# 407-cpu.net
KiCad netlist of a schematic drawn in Altium Designer
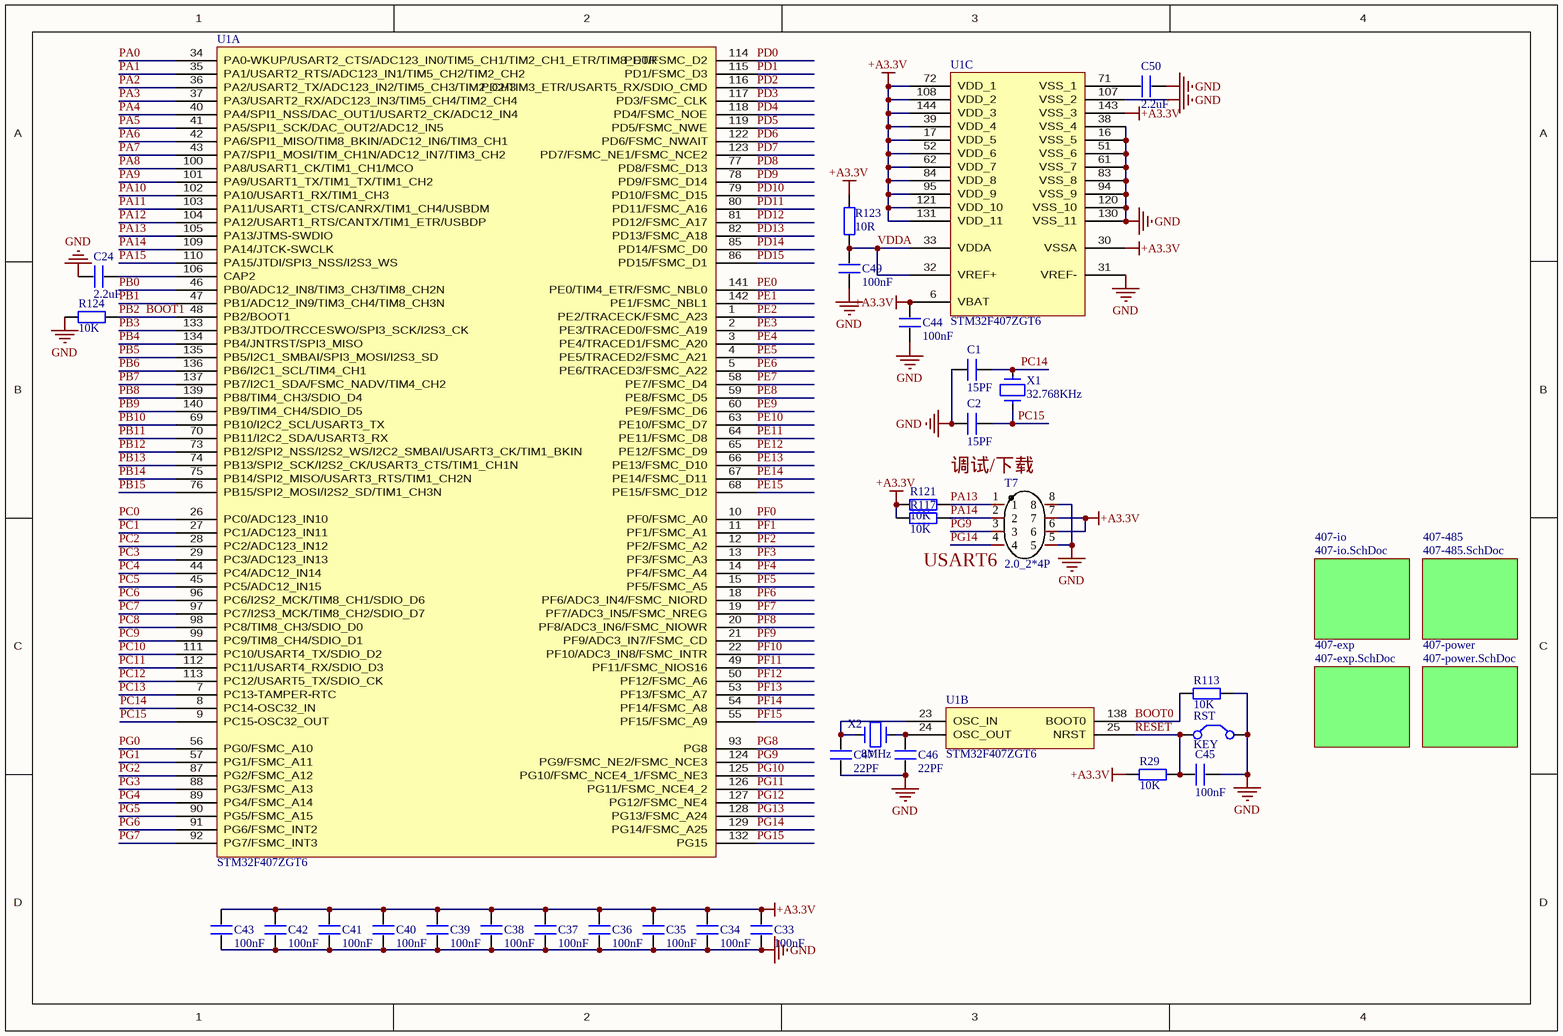
[diagram p0: 407-cpu .schdoc]

(export (version "E")
  (design (tool "Eeschema 10.0.6"))
  (components
    (comp (ref "C1") (value "15PF") (libsource (lib "驱动库") (part "C")))
    (comp (ref "C2") (value "15PF") (libsource (lib "驱动库") (part "C")))
    (comp (ref "C24") (value "2.2uF") (libsource (lib "驱动库") (part "C")))
    (comp (ref "C33") (value "100nF") (libsource (lib "驱动库") (part "C")))
    (comp (ref "C34") (value "100nF") (libsource (lib "驱动库") (part "C")))
    (comp (ref "C35") (value "100nF") (libsource (lib "驱动库") (part "C")))
    (comp (ref "C36") (value "100nF") (libsource (lib "驱动库") (part "C")))
    (comp (ref "C37") (value "100nF") (libsource (lib "驱动库") (part "C")))
    (comp (ref "C38") (value "100nF") (libsource (lib "驱动库") (part "C")))
    (comp (ref "C39") (value "100nF") (libsource (lib "驱动库") (part "C")))
    (comp (ref "C40") (value "100nF") (libsource (lib "驱动库") (part "C")))
    (comp (ref "C41") (value "100nF") (libsource (lib "驱动库") (part "C")))
    (comp (ref "C42") (value "100nF") (libsource (lib "驱动库") (part "C")))
    (comp (ref "C43") (value "100nF") (libsource (lib "驱动库") (part "C")))
    (comp (ref "C44") (value "100nF") (libsource (lib "驱动库") (part "C")))
    (comp (ref "C45") (value "100nF") (libsource (lib "驱动库") (part "C")))
    (comp (ref "C46") (value "22PF") (libsource (lib "驱动库") (part "C")))
    (comp (ref "C47") (value "22PF") (libsource (lib "驱动库") (part "C")))
    (comp (ref "C49") (value "100nF") (libsource (lib "驱动库") (part "C")))
    (comp (ref "C50") (value "2.2uF") (libsource (lib "驱动库") (part "C")))
    (comp (ref "R29") (value "10K") (description "Resistor") (libsource (lib "STM32F103ZE") (part "Res2")))
    (comp (ref "R113") (value "10K") (description "Resistor") (libsource (lib "STM32F103ZE") (part "Res2")))
    (comp (ref "R117") (value "10K") (description "Resistor") (libsource (lib "") (part "Res2_1")))
    (comp (ref "R121") (value "10K") (description "Resistor") (libsource (lib "") (part "Res2_1")))
    (comp (ref "R123") (value "10R") (description "Resistor") (libsource (lib "") (part "Res2_2")))
    (comp (ref "R124") (value "10K") (description "Resistor") (libsource (lib "STM32F103ZE") (part "Res2")))
    (comp (ref "RST")
      (value "KEY")
      (description "Jumper Wire")
      (fields (field (name "PUBLISHER") "Altium Limited"))
      (libsource (lib "STM32F103ZE") (part "Jumper"))
    )
    (comp (ref "T7")
      (value "2.0_2*4P")
      (footprint "2.0_2*4P")
      (libsource (lib "tianjin_2023") (part "2.0_2*4P"))
    )
    (comp (ref "U1") (value "STM32F407ZGT6") (libsource (lib "STM32F103ZE") (part "STM32F103ZET6_1")))
    (comp (ref "X1")
      (value "32.768KHz")
      (description "Crystal Oscillator")
      (libsource (lib "STM32F103ZE") (part "XTAL"))
    )
    (comp (ref "X2")
      (value "8MHz")
      (description "Crystal Oscillator")
      (libsource (lib "STM32F103ZE") (part "XTAL"))
    )
  )
  (nets
    (net (code "1") (name "+A3.3V") (class "Default")
      (node (ref "C33") (pin "2") (pintype "passive"))
      (node (ref "C34") (pin "2") (pintype "passive"))
      (node (ref "C35") (pin "2") (pintype "passive"))
      (node (ref "C36") (pin "2") (pintype "passive"))
      (node (ref "C37") (pin "2") (pintype "passive"))
      (node (ref "C38") (pin "2") (pintype "passive"))
      (node (ref "C39") (pin "2") (pintype "passive"))
      (node (ref "C40") (pin "2") (pintype "passive"))
      (node (ref "C41") (pin "2") (pintype "passive"))
      (node (ref "C42") (pin "2") (pintype "passive"))
      (node (ref "C43") (pin "2") (pintype "passive"))
      (node (ref "C44") (pin "2") (pintype "passive"))
      (node (ref "R117") (pin "2") (pinfunction "2_2") (pintype "passive"))
      (node (ref "R121") (pin "2") (pinfunction "2_2") (pintype "passive"))
      (node (ref "R123") (pin "1") (pinfunction "1_1") (pintype "passive"))
      (node (ref "R29") (pin "1") (pinfunction "1_1") (pintype "passive"))
      (node (ref "T7") (pin "6") (pinfunction "6_6") (pintype "passive"))
      (node (ref "T7") (pin "7") (pinfunction "7_7") (pintype "passive"))
      (node (ref "U1") (pin "108") (pinfunction "VDD_2_108") (pintype "passive"))
      (node (ref "U1") (pin "121") (pinfunction "VDD_10_121") (pintype "passive"))
      (node (ref "U1") (pin "131") (pinfunction "VDD_11_131") (pintype "passive"))
      (node (ref "U1") (pin "143") (pinfunction "VSS_3_143") (pintype "passive"))
      (node (ref "U1") (pin "144") (pinfunction "VDD_3_144") (pintype "passive"))
      (node (ref "U1") (pin "17") (pinfunction "VDD_5_17") (pintype "passive"))
      (node (ref "U1") (pin "30") (pinfunction "VSSA_30") (pintype "passive"))
      (node (ref "U1") (pin "39") (pinfunction "VDD_4_39") (pintype "passive"))
      (node (ref "U1") (pin "52") (pinfunction "VDD_6_52") (pintype "passive"))
      (node (ref "U1") (pin "6") (pinfunction "VBAT_6") (pintype "passive"))
      (node (ref "U1") (pin "62") (pinfunction "VDD_7_62") (pintype "passive"))
      (node (ref "U1") (pin "72") (pinfunction "VDD_1_72") (pintype "passive"))
      (node (ref "U1") (pin "84") (pinfunction "VDD_8_84") (pintype "passive"))
      (node (ref "U1") (pin "95") (pinfunction "VDD_9_95") (pintype "passive"))
    )
    (net (code "3") (name "/BOOT0") (class "Default")
      (node (ref "R113") (pin "1") (pinfunction "1_1") (pintype "passive"))
      (node (ref "U1") (pin "138") (pinfunction "BOOT0_138") (pintype "passive"))
    )
    (net (code "4") (name "/BOOT1") (class "Default")
      (node (ref "R124") (pin "2") (pinfunction "2_2") (pintype "passive"))
      (node (ref "U1") (pin "48") (pinfunction "PB2/BOOT1_48") (pintype "passive"))
    )
    (net (code "5") (name "/PA0") (class "Default")
      (node (ref "U1") (pin "34") (pinfunction "PA0-WKUP/USART2_CTS/ADC123_IN0/TIM5_CH1/TIM2_CH1_ETR/TIM8_ETR_34") (pintype "passive"))
    )
    (net (code "6") (name "/PA1") (class "Default")
      (node (ref "U1") (pin "35") (pinfunction "PA1/USART2_RTS/ADC123_IN1/TIM5_CH2/TIM2_CH2_35") (pintype "passive"))
    )
    (net (code "7") (name "/PA2") (class "Default")
      (node (ref "U1") (pin "36") (pinfunction "PA2/USART2_TX/ADC123_IN2/TIM5_CH3/TIM2_CH3_36") (pintype "passive"))
    )
    (net (code "8") (name "/PA3") (class "Default")
      (node (ref "U1") (pin "37") (pinfunction "PA3/USART2_RX/ADC123_IN3/TIM5_CH4/TIM2_CH4_37") (pintype "passive"))
    )
    (net (code "9") (name "/PA4") (class "Default")
      (node (ref "U1") (pin "40") (pinfunction "PA4/SPI1_NSS/DAC_OUT1/USART2_CK/ADC12_IN4_40") (pintype "passive"))
    )
    (net (code "10") (name "/PA5") (class "Default")
      (node (ref "U1") (pin "41") (pinfunction "PA5/SPI1_SCK/DAC_OUT2/ADC12_IN5_41") (pintype "passive"))
    )
    (net (code "11") (name "/PA6") (class "Default")
      (node (ref "U1") (pin "42") (pinfunction "PA6/SPI1_MISO/TIM8_BKIN/ADC12_IN6/TIM3_CH1_42") (pintype "passive"))
    )
    (net (code "12") (name "/PA7") (class "Default")
      (node (ref "U1") (pin "43") (pinfunction "PA7/SPI1_MOSI/TIM_CH1N/ADC12_IN7/TIM3_CH2_43") (pintype "passive"))
    )
    (net (code "13") (name "/PA8") (class "Default")
      (node (ref "U1") (pin "100") (pinfunction "PA8/USART1_CK/TIM1_CH1/MCO_100") (pintype "passive"))
    )
    (net (code "14") (name "/PA9") (class "Default")
      (node (ref "U1") (pin "101") (pinfunction "PA9/USART1_TX/TIM1_TX/TIM1_CH2_101") (pintype "passive"))
    )
    (net (code "15") (name "/PA10") (class "Default")
      (node (ref "U1") (pin "102") (pinfunction "PA10/USART1_RX/TIM1_CH3_102") (pintype "passive"))
    )
    (net (code "16") (name "/PA11") (class "Default")
      (node (ref "U1") (pin "103") (pinfunction "PA11/USART1_CTS/CANRX/TIM1_CH4/USBDM_103") (pintype "passive"))
    )
    (net (code "17") (name "/PA12") (class "Default")
      (node (ref "U1") (pin "104") (pinfunction "PA12/USART1_RTS/CANTX/TIM1_ETR/USBDP_104") (pintype "passive"))
    )
    (net (code "18") (name "/PA13") (class "Default")
      (node (ref "R121") (pin "1") (pinfunction "1_1") (pintype "passive"))
      (node (ref "T7") (pin "1") (pinfunction "1_1") (pintype "passive"))
      (node (ref "U1") (pin "105") (pinfunction "PA13/JTMS-SWDIO_105") (pintype "passive"))
    )
    (net (code "19") (name "/PA14") (class "Default")
      (node (ref "R117") (pin "1") (pinfunction "1_1") (pintype "passive"))
      (node (ref "T7") (pin "2") (pinfunction "2_2") (pintype "passive"))
      (node (ref "U1") (pin "109") (pinfunction "PA14/JTCK-SWCLK_109") (pintype "passive"))
    )
    (net (code "20") (name "/PA15") (class "Default")
      (node (ref "U1") (pin "110") (pinfunction "PA15/JTDI/SPI3_NSS/I2S3_WS_110") (pintype "passive"))
    )
    (net (code "21") (name "/PB0") (class "Default")
      (node (ref "U1") (pin "46") (pinfunction "PB0/ADC12_IN8/TIM3_CH3/TIM8_CH2N_46") (pintype "passive"))
    )
    (net (code "22") (name "/PB1") (class "Default")
      (node (ref "U1") (pin "47") (pinfunction "PB1/ADC12_IN9/TIM3_CH4/TIM8_CH3N_47") (pintype "passive"))
    )
    (net (code "23") (name "/PB3") (class "Default")
      (node (ref "U1") (pin "133") (pinfunction "PB3/JTDO/TRCCESWO/SPI3_SCK/I2S3_CK_133") (pintype "passive"))
    )
    (net (code "24") (name "/PB4") (class "Default")
      (node (ref "U1") (pin "134") (pinfunction "PB4/JNTRST/SPI3_MISO_134") (pintype "passive"))
    )
    (net (code "25") (name "/PB5") (class "Default")
      (node (ref "U1") (pin "135") (pinfunction "PB5/I2C1_SMBAI/SPI3_MOSI/I2S3_SD_135") (pintype "passive"))
    )
    (net (code "26") (name "/PB6") (class "Default")
      (node (ref "U1") (pin "136") (pinfunction "PB6/I2C1_SCL/TIM4_CH1_136") (pintype "passive"))
    )
    (net (code "27") (name "/PB7") (class "Default")
      (node (ref "U1") (pin "137") (pinfunction "PB7/I2C1_SDA/FSMC_NADV/TIM4_CH2_137") (pintype "passive"))
    )
    (net (code "28") (name "/PB8") (class "Default")
      (node (ref "U1") (pin "139") (pinfunction "PB8/TIM4_CH3/SDIO_D4_139") (pintype "passive"))
    )
    (net (code "29") (name "/PB9") (class "Default")
      (node (ref "U1") (pin "140") (pinfunction "PB9/TIM4_CH4/SDIO_D5_140") (pintype "passive"))
    )
    (net (code "30") (name "/PB10") (class "Default")
      (node (ref "U1") (pin "69") (pinfunction "PB10/I2C2_SCL/USART3_TX_69") (pintype "passive"))
    )
    (net (code "31") (name "/PB11") (class "Default")
      (node (ref "U1") (pin "70") (pinfunction "PB11/I2C2_SDA/USART3_RX_70") (pintype "passive"))
    )
    (net (code "32") (name "/PB12") (class "Default")
      (node (ref "U1") (pin "73") (pinfunction "PB12/SPI2_NSS/I2S2_WS/I2C2_SMBAI/USART3_CK/TIM1_BKIN_73") (pintype "passive"))
    )
    (net (code "33") (name "/PB13") (class "Default")
      (node (ref "U1") (pin "74") (pinfunction "PB13/SPI2_SCK/I2S2_CK/USART3_CTS/TIM1_CH1N_74") (pintype "passive"))
    )
    (net (code "34") (name "/PB14") (class "Default")
      (node (ref "U1") (pin "75") (pinfunction "PB14/SPI2_MISO/USART3_RTS/TIM1_CH2N_75") (pintype "passive"))
    )
    (net (code "35") (name "/PB15") (class "Default")
      (node (ref "U1") (pin "76") (pinfunction "PB15/SPI2_MOSI/I2S2_SD/TIM1_CH3N_76") (pintype "passive"))
    )
    (net (code "36") (name "/PC0") (class "Default")
      (node (ref "U1") (pin "26") (pinfunction "PC0/ADC123_IN10_26") (pintype "passive"))
    )
    (net (code "37") (name "/PC1") (class "Default")
      (node (ref "U1") (pin "27") (pinfunction "PC1/ADC123_IN11_27") (pintype "passive"))
    )
    (net (code "38") (name "/PC2") (class "Default")
      (node (ref "U1") (pin "28") (pinfunction "PC2/ADC123_IN12_28") (pintype "passive"))
    )
    (net (code "39") (name "/PC3") (class "Default")
      (node (ref "U1") (pin "29") (pinfunction "PC3/ADC123_IN13_29") (pintype "passive"))
    )
    (net (code "40") (name "/PC4") (class "Default")
      (node (ref "U1") (pin "44") (pinfunction "PC4/ADC12_IN14_44") (pintype "passive"))
    )
    (net (code "41") (name "/PC5") (class "Default")
      (node (ref "U1") (pin "45") (pinfunction "PC5/ADC12_IN15_45") (pintype "passive"))
    )
    (net (code "42") (name "/PC6") (class "Default")
      (node (ref "U1") (pin "96") (pinfunction "PC6/I2S2_MCK/TIM8_CH1/SDIO_D6_96") (pintype "passive"))
    )
    (net (code "43") (name "/PC7") (class "Default")
      (node (ref "U1") (pin "97") (pinfunction "PC7/I2S3_MCK/TIM8_CH2/SDIO_D7_97") (pintype "passive"))
    )
    (net (code "44") (name "/PC8") (class "Default")
      (node (ref "U1") (pin "98") (pinfunction "PC8/TIM8_CH3/SDIO_D0_98") (pintype "passive"))
    )
    (net (code "45") (name "/PC9") (class "Default")
      (node (ref "U1") (pin "99") (pinfunction "PC9/TIM8_CH4/SDIO_D1_99") (pintype "passive"))
    )
    (net (code "46") (name "/PC10") (class "Default")
      (node (ref "U1") (pin "111") (pinfunction "PC10/USART4_TX/SDIO_D2_111") (pintype "passive"))
    )
    (net (code "47") (name "/PC11") (class "Default")
      (node (ref "U1") (pin "112") (pinfunction "PC11/USART4_RX/SDIO_D3_112") (pintype "passive"))
    )
    (net (code "48") (name "/PC12") (class "Default")
      (node (ref "U1") (pin "113") (pinfunction "PC12/USART5_TX/SDIO_CK_113") (pintype "passive"))
    )
    (net (code "49") (name "/PC13") (class "Default")
      (node (ref "U1") (pin "7") (pinfunction "PC13-TAMPER-RTC_7") (pintype "passive"))
    )
    (net (code "50") (name "/PC14") (class "Default")
      (node (ref "C1") (pin "1") (pintype "passive"))
      (node (ref "U1") (pin "8") (pinfunction "PC14-OSC32_IN_8") (pintype "passive"))
      (node (ref "X1") (pin "1") (pinfunction "1_1") (pintype "passive"))
    )
    (net (code "51") (name "/PC15") (class "Default")
      (node (ref "C2") (pin "1") (pintype "passive"))
      (node (ref "U1") (pin "9") (pinfunction "PC15-OSC32_OUT_9") (pintype "passive"))
      (node (ref "X1") (pin "2") (pinfunction "2_2") (pintype "passive"))
    )
    (net (code "52") (name "/PD0") (class "Default")
      (node (ref "U1") (pin "114") (pinfunction "PD0/FSMC_D2_114") (pintype "passive"))
    )
    (net (code "53") (name "/PD1") (class "Default")
      (node (ref "U1") (pin "115") (pinfunction "PD1/FSMC_D3_115") (pintype "passive"))
    )
    (net (code "54") (name "/PD2") (class "Default")
      (node (ref "U1") (pin "116") (pinfunction "PD2/TIM3_ETR/USART5_RX/SDIO_CMD_116") (pintype "passive"))
    )
    (net (code "55") (name "/PD3") (class "Default")
      (node (ref "U1") (pin "117") (pinfunction "PD3/FSMC_CLK_117") (pintype "passive"))
    )
    (net (code "56") (name "/PD4") (class "Default")
      (node (ref "U1") (pin "118") (pinfunction "PD4/FSMC_NOE_118") (pintype "passive"))
    )
    (net (code "57") (name "/PD5") (class "Default")
      (node (ref "U1") (pin "119") (pinfunction "PD5/FSMC_NWE_119") (pintype "passive"))
    )
    (net (code "58") (name "/PD6") (class "Default")
      (node (ref "U1") (pin "122") (pinfunction "PD6/FSMC_NWAIT_122") (pintype "passive"))
    )
    (net (code "59") (name "/PD7") (class "Default")
      (node (ref "U1") (pin "123") (pinfunction "PD7/FSMC_NE1/FSMC_NCE2_123") (pintype "passive"))
    )
    (net (code "60") (name "/PD8") (class "Default")
      (node (ref "U1") (pin "77") (pinfunction "PD8/FSMC_D13_77") (pintype "passive"))
    )
    (net (code "61") (name "/PD9") (class "Default")
      (node (ref "U1") (pin "78") (pinfunction "PD9/FSMC_D14_78") (pintype "passive"))
    )
    (net (code "62") (name "/PD10") (class "Default")
      (node (ref "U1") (pin "79") (pinfunction "PD10/FSMC_D15_79") (pintype "passive"))
    )
    (net (code "63") (name "/PD11") (class "Default")
      (node (ref "U1") (pin "80") (pinfunction "PD11/FSMC_A16_80") (pintype "passive"))
    )
    (net (code "64") (name "/PD12") (class "Default")
      (node (ref "U1") (pin "81") (pinfunction "PD12/FSMC_A17_81") (pintype "passive"))
    )
    (net (code "65") (name "/PD13") (class "Default")
      (node (ref "U1") (pin "82") (pinfunction "PD13/FSMC_A18_82") (pintype "passive"))
    )
    (net (code "66") (name "/PD14") (class "Default")
      (node (ref "U1") (pin "85") (pinfunction "PD14/FSMC_D0_85") (pintype "passive"))
    )
    (net (code "67") (name "/PD15") (class "Default")
      (node (ref "U1") (pin "86") (pinfunction "PD15/FSMC_D1_86") (pintype "passive"))
    )
    (net (code "68") (name "/PE0") (class "Default")
      (node (ref "U1") (pin "141") (pinfunction "PE0/TIM4_ETR/FSMC_NBL0_141") (pintype "passive"))
    )
    (net (code "69") (name "/PE1") (class "Default")
      (node (ref "U1") (pin "142") (pinfunction "PE1/FSMC_NBL1_142") (pintype "passive"))
    )
    (net (code "70") (name "/PE2") (class "Default")
      (node (ref "U1") (pin "1") (pinfunction "PE2/TRACECK/FSMC_A23_1") (pintype "passive"))
    )
    (net (code "71") (name "/PE3") (class "Default")
      (node (ref "U1") (pin "2") (pinfunction "PE3/TRACED0/FSMC_A19_2") (pintype "passive"))
    )
    (net (code "72") (name "/PE4") (class "Default")
      (node (ref "U1") (pin "3") (pinfunction "PE4/TRACED1/FSMC_A20_3") (pintype "passive"))
    )
    (net (code "73") (name "/PE5") (class "Default")
      (node (ref "U1") (pin "4") (pinfunction "PE5/TRACED2/FSMC_A21_4") (pintype "passive"))
    )
    (net (code "74") (name "/PE6") (class "Default")
      (node (ref "U1") (pin "5") (pinfunction "PE6/TRACED3/FSMC_A22_5") (pintype "passive"))
    )
    (net (code "75") (name "/PE7") (class "Default")
      (node (ref "U1") (pin "58") (pinfunction "PE7/FSMC_D4_58") (pintype "passive"))
    )
    (net (code "76") (name "/PE8") (class "Default")
      (node (ref "U1") (pin "59") (pinfunction "PE8/FSMC_D5_59") (pintype "passive"))
    )
    (net (code "77") (name "/PE9") (class "Default")
      (node (ref "U1") (pin "60") (pinfunction "PE9/FSMC_D6_60") (pintype "passive"))
    )
    (net (code "78") (name "/PE10") (class "Default")
      (node (ref "U1") (pin "63") (pinfunction "PE10/FSMC_D7_63") (pintype "passive"))
    )
    (net (code "79") (name "/PE11") (class "Default")
      (node (ref "U1") (pin "64") (pinfunction "PE11/FSMC_D8_64") (pintype "passive"))
    )
    (net (code "80") (name "/PE12") (class "Default")
      (node (ref "U1") (pin "65") (pinfunction "PE12/FSMC_D9_65") (pintype "passive"))
    )
    (net (code "81") (name "/PE13") (class "Default")
      (node (ref "U1") (pin "66") (pinfunction "PE13/FSMC_D10_66") (pintype "passive"))
    )
    (net (code "82") (name "/PE14") (class "Default")
      (node (ref "U1") (pin "67") (pinfunction "PE14/FSMC_D11_67") (pintype "passive"))
    )
    (net (code "83") (name "/PE15") (class "Default")
      (node (ref "U1") (pin "68") (pinfunction "PE15/FSMC_D12_68") (pintype "passive"))
    )
    (net (code "84") (name "/PF0") (class "Default")
      (node (ref "U1") (pin "10") (pinfunction "PF0/FSMC_A0_10") (pintype "passive"))
    )
    (net (code "85") (name "/PF1") (class "Default")
      (node (ref "U1") (pin "11") (pinfunction "PF1/FSMC_A1_11") (pintype "passive"))
    )
    (net (code "86") (name "/PF2") (class "Default")
      (node (ref "U1") (pin "12") (pinfunction "PF2/FSMC_A2_12") (pintype "passive"))
    )
    (net (code "87") (name "/PF3") (class "Default")
      (node (ref "U1") (pin "13") (pinfunction "PF3/FSMC_A3_13") (pintype "passive"))
    )
    (net (code "88") (name "/PF4") (class "Default")
      (node (ref "U1") (pin "14") (pinfunction "PF4/FSMC_A4_14") (pintype "passive"))
    )
    (net (code "89") (name "/PF5") (class "Default")
      (node (ref "U1") (pin "15") (pinfunction "PF5/FSMC_A5_15") (pintype "passive"))
    )
    (net (code "90") (name "/PF6") (class "Default")
      (node (ref "U1") (pin "18") (pinfunction "PF6/ADC3_IN4/FSMC_NIORD_18") (pintype "passive"))
    )
    (net (code "91") (name "/PF7") (class "Default")
      (node (ref "U1") (pin "19") (pinfunction "PF7/ADC3_IN5/FSMC_NREG_19") (pintype "passive"))
    )
    (net (code "92") (name "/PF8") (class "Default")
      (node (ref "U1") (pin "20") (pinfunction "PF8/ADC3_IN6/FSMC_NIOWR_20") (pintype "passive"))
    )
    (net (code "93") (name "/PF9") (class "Default")
      (node (ref "U1") (pin "21") (pinfunction "PF9/ADC3_IN7/FSMC_CD_21") (pintype "passive"))
    )
    (net (code "94") (name "/PF10") (class "Default")
      (node (ref "U1") (pin "22") (pinfunction "PF10/ADC3_IN8/FSMC_INTR_22") (pintype "passive"))
    )
    (net (code "95") (name "/PF11") (class "Default")
      (node (ref "U1") (pin "49") (pinfunction "PF11/FSMC_NIOS16_49") (pintype "passive"))
    )
    (net (code "96") (name "/PF12") (class "Default")
      (node (ref "U1") (pin "50") (pinfunction "PF12/FSMC_A6_50") (pintype "passive"))
    )
    (net (code "97") (name "/PF13") (class "Default")
      (node (ref "U1") (pin "53") (pinfunction "PF13/FSMC_A7_53") (pintype "passive"))
    )
    (net (code "98") (name "/PF14") (class "Default")
      (node (ref "U1") (pin "54") (pinfunction "PF14/FSMC_A8_54") (pintype "passive"))
    )
    (net (code "99") (name "/PF15") (class "Default")
      (node (ref "U1") (pin "55") (pinfunction "PF15/FSMC_A9_55") (pintype "passive"))
    )
    (net (code "100") (name "/PG0") (class "Default")
      (node (ref "U1") (pin "56") (pinfunction "PG0/FSMC_A10_56") (pintype "passive"))
    )
    (net (code "101") (name "/PG1") (class "Default")
      (node (ref "U1") (pin "57") (pinfunction "PG1/FSMC_A11_57") (pintype "passive"))
    )
    (net (code "102") (name "/PG2") (class "Default")
      (node (ref "U1") (pin "87") (pinfunction "PG2/FSMC_A12_87") (pintype "passive"))
    )
    (net (code "103") (name "/PG3") (class "Default")
      (node (ref "U1") (pin "88") (pinfunction "PG3/FSMC_A13_88") (pintype "passive"))
    )
    (net (code "104") (name "/PG4") (class "Default")
      (node (ref "U1") (pin "89") (pinfunction "PG4/FSMC_A14_89") (pintype "passive"))
    )
    (net (code "105") (name "/PG5") (class "Default")
      (node (ref "U1") (pin "90") (pinfunction "PG5/FSMC_A15_90") (pintype "passive"))
    )
    (net (code "106") (name "/PG6") (class "Default")
      (node (ref "U1") (pin "91") (pinfunction "PG6/FSMC_INT2_91") (pintype "passive"))
    )
    (net (code "107") (name "/PG7") (class "Default")
      (node (ref "U1") (pin "92") (pinfunction "PG7/FSMC_INT3_92") (pintype "passive"))
    )
    (net (code "108") (name "/PG8") (class "Default")
      (node (ref "U1") (pin "93") (pinfunction "PG8_93") (pintype "passive"))
    )
    (net (code "109") (name "/PG9") (class "Default")
      (node (ref "T7") (pin "3") (pinfunction "3_3") (pintype "passive"))
      (node (ref "U1") (pin "124") (pinfunction "PG9/FSMC_NE2/FSMC_NCE3_124") (pintype "passive"))
    )
    (net (code "110") (name "/PG10") (class "Default")
      (node (ref "U1") (pin "125") (pinfunction "PG10/FSMC_NCE4_1/FSMC_NE3_125") (pintype "passive"))
    )
    (net (code "111") (name "/PG11") (class "Default")
      (node (ref "U1") (pin "126") (pinfunction "PG11/FSMC_NCE4_2_126") (pintype "passive"))
    )
    (net (code "112") (name "/PG12") (class "Default")
      (node (ref "U1") (pin "127") (pinfunction "PG12/FSMC_NE4_127") (pintype "passive"))
    )
    (net (code "113") (name "/PG13") (class "Default")
      (node (ref "U1") (pin "128") (pinfunction "PG13/FSMC_A24_128") (pintype "passive"))
    )
    (net (code "114") (name "/PG14") (class "Default")
      (node (ref "T7") (pin "4") (pinfunction "4_4") (pintype "passive"))
      (node (ref "U1") (pin "129") (pinfunction "PG14/FSMC_A25_129") (pintype "passive"))
    )
    (net (code "115") (name "/PG15") (class "Default")
      (node (ref "U1") (pin "132") (pinfunction "PG15_132") (pintype "passive"))
    )
    (net (code "116") (name "/RESET") (class "Default")
      (node (ref "C45") (pin "2") (pintype "passive"))
      (node (ref "R29") (pin "2") (pinfunction "2_2") (pintype "passive"))
      (node (ref "RST") (pin "1") (pinfunction "C1_1") (pintype "passive"))
      (node (ref "U1") (pin "25") (pinfunction "NRST_25") (pintype "passive"))
    )
    (net (code "117") (name "/VDDA") (class "Default")
      (node (ref "C49") (pin "2") (pintype "passive"))
      (node (ref "R123") (pin "2") (pinfunction "2_2") (pintype "passive"))
      (node (ref "U1") (pin "32") (pinfunction "VREF+_32") (pintype "passive"))
      (node (ref "U1") (pin "33") (pinfunction "VDDA_33") (pintype "passive"))
    )
    (net (code "118") (name "GND") (class "Default")
      (node (ref "C1") (pin "2") (pintype "passive"))
      (node (ref "C2") (pin "2") (pintype "passive"))
      (node (ref "C24") (pin "1") (pintype "passive"))
      (node (ref "C33") (pin "1") (pintype "passive"))
      (node (ref "C34") (pin "1") (pintype "passive"))
      (node (ref "C35") (pin "1") (pintype "passive"))
      (node (ref "C36") (pin "1") (pintype "passive"))
      (node (ref "C37") (pin "1") (pintype "passive"))
      (node (ref "C38") (pin "1") (pintype "passive"))
      (node (ref "C39") (pin "1") (pintype "passive"))
      (node (ref "C40") (pin "1") (pintype "passive"))
      (node (ref "C41") (pin "1") (pintype "passive"))
      (node (ref "C42") (pin "1") (pintype "passive"))
      (node (ref "C43") (pin "1") (pintype "passive"))
      (node (ref "C44") (pin "1") (pintype "passive"))
      (node (ref "C45") (pin "1") (pintype "passive"))
      (node (ref "C46") (pin "1") (pintype "passive"))
      (node (ref "C47") (pin "1") (pintype "passive"))
      (node (ref "C49") (pin "1") (pintype "passive"))
      (node (ref "C50") (pin "2") (pintype "passive"))
      (node (ref "R113") (pin "2") (pinfunction "2_2") (pintype "passive"))
      (node (ref "R124") (pin "1") (pinfunction "1_1") (pintype "passive"))
      (node (ref "RST") (pin "2") (pinfunction "C2_2") (pintype "passive"))
      (node (ref "T7") (pin "5") (pinfunction "5_5") (pintype "passive"))
      (node (ref "T7") (pin "8") (pinfunction "8_8") (pintype "passive"))
      (node (ref "U1") (pin "107") (pinfunction "VSS_2_107") (pintype "passive"))
      (node (ref "U1") (pin "120") (pinfunction "VSS_10_120") (pintype "passive"))
      (node (ref "U1") (pin "130") (pinfunction "VSS_11_130") (pintype "passive"))
      (node (ref "U1") (pin "16") (pinfunction "VSS_5_16") (pintype "passive"))
      (node (ref "U1") (pin "31") (pinfunction "VREF-_31") (pintype "passive"))
      (node (ref "U1") (pin "38") (pinfunction "VSS_4_38") (pintype "passive"))
      (node (ref "U1") (pin "51") (pinfunction "VSS_6_51") (pintype "passive"))
      (node (ref "U1") (pin "61") (pinfunction "VSS_7_61") (pintype "passive"))
      (node (ref "U1") (pin "83") (pinfunction "VSS_8_83") (pintype "passive"))
      (node (ref "U1") (pin "94") (pinfunction "VSS_9_94") (pintype "passive"))
    )
    (net (code "119") (name "Net-(U1A-CAP2)") (class "Default")
      (node (ref "C24") (pin "2") (pintype "passive"))
      (node (ref "U1") (pin "106") (pinfunction "CAP2_106") (pintype "passive"))
    )
    (net (code "120") (name "Net-(U1B-OSC_IN)") (class "Default")
      (node (ref "C47") (pin "2") (pintype "passive"))
      (node (ref "U1") (pin "23") (pinfunction "OSC_IN_23") (pintype "passive"))
      (node (ref "X2") (pin "1") (pinfunction "1_1") (pintype "passive"))
    )
    (net (code "121") (name "Net-(U1B-OSC_OUT)") (class "Default")
      (node (ref "C46") (pin "2") (pintype "passive"))
      (node (ref "U1") (pin "24") (pinfunction "OSC_OUT_24") (pintype "passive"))
      (node (ref "X2") (pin "2") (pinfunction "2_2") (pintype "passive"))
    )
    (net (code "122") (name "Net-(U1C-VSS_1)") (class "Default")
      (node (ref "C50") (pin "1") (pintype "passive"))
      (node (ref "U1") (pin "71") (pinfunction "VSS_1_71") (pintype "passive"))
    )
  )
)
